# Modulo_shield_L6470-28.net
KiCad netlist of a schematic drawn in EAGLE
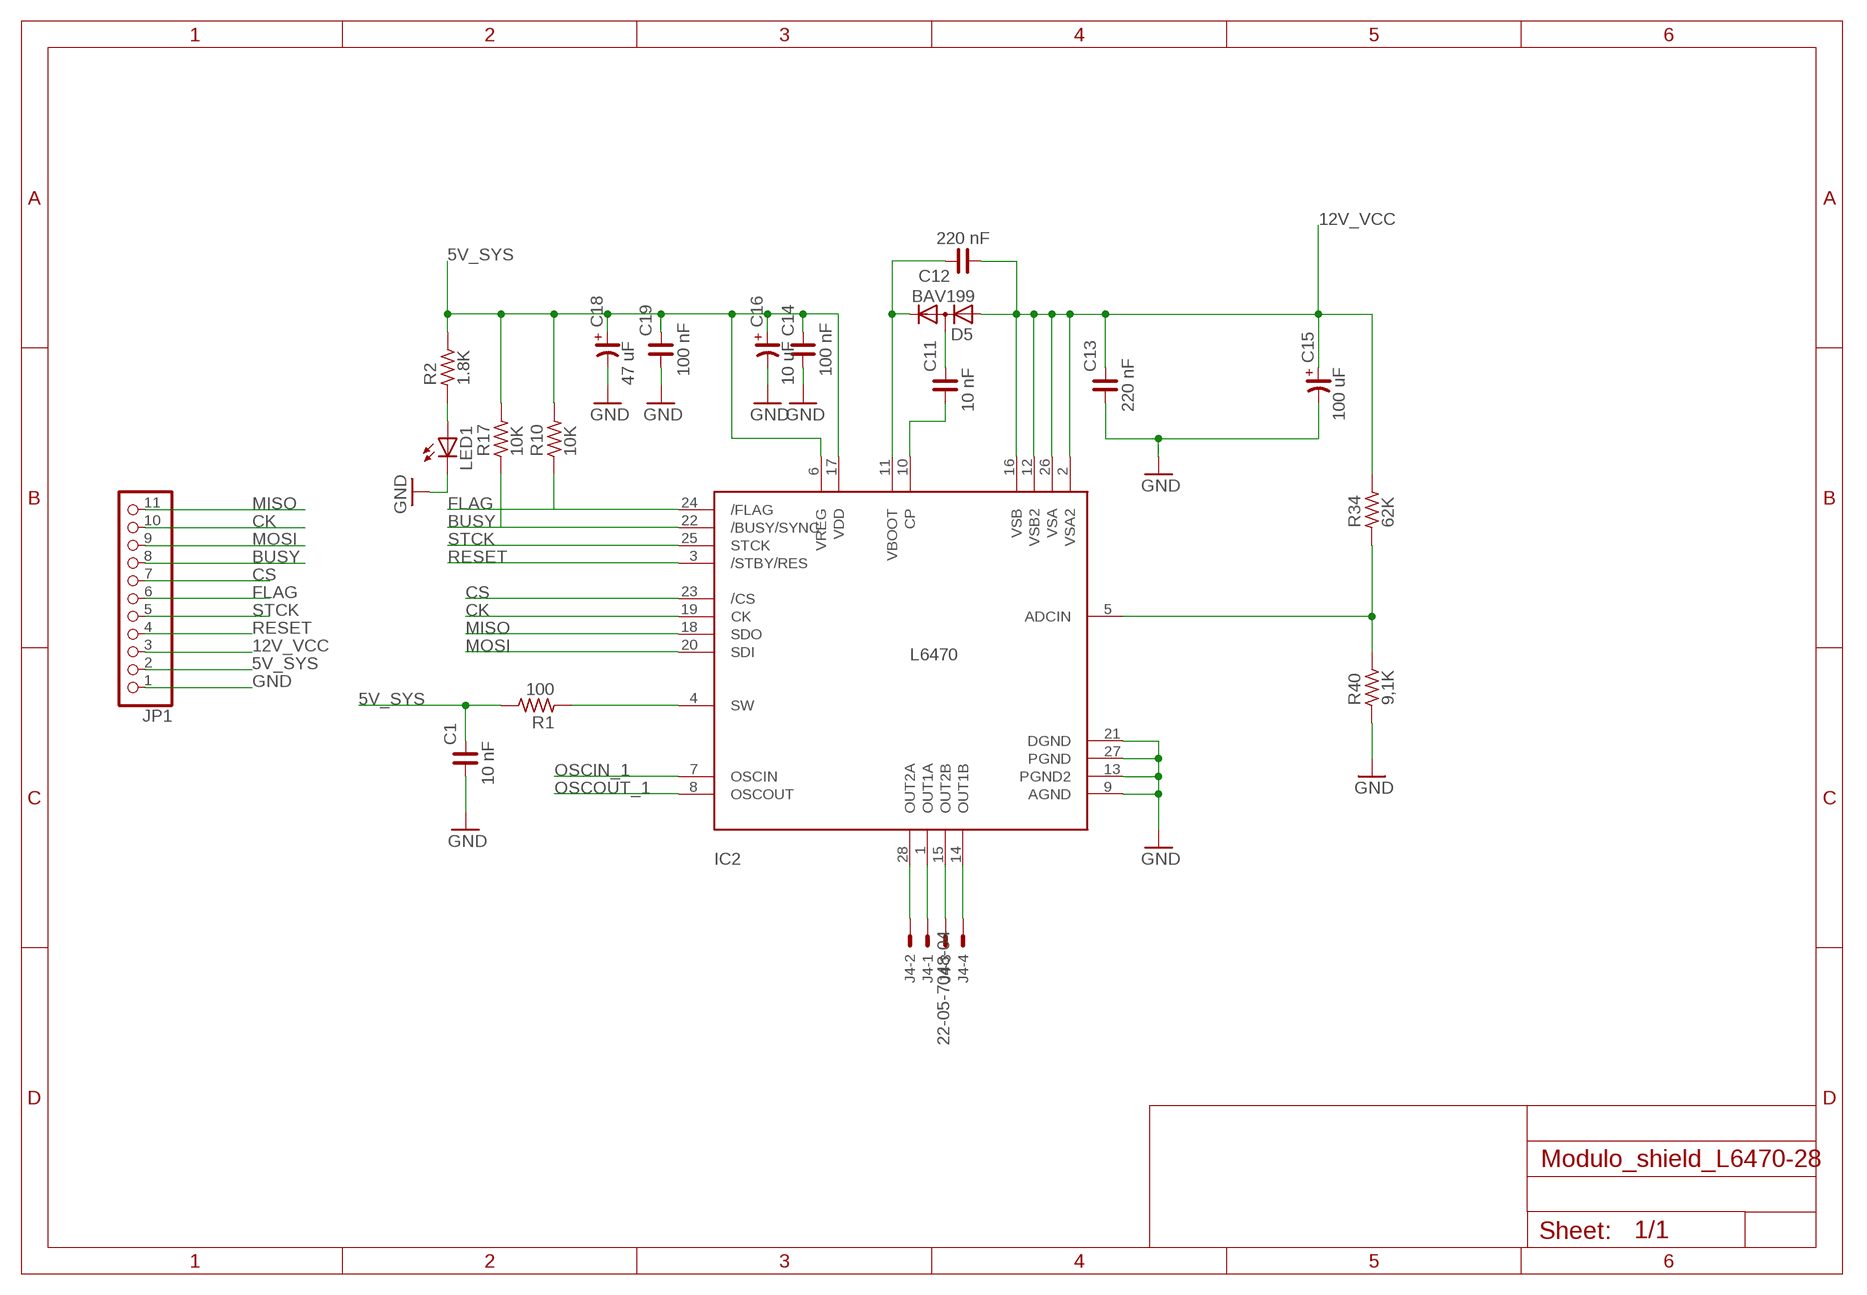
[diagram p0: schematic, sheet 1]

(export (version "E")
  (design (tool "Eeschema 10.0.6"))
  (components
    (comp (ref "C1")
      (value "10 nF")
      (footprint "eagle-import:C1206")
      (libsource (lib "eagle-import") (part "C_1206"))
    )
    (comp (ref "C11")
      (value "10 nF")
      (footprint "eagle-import:C1206")
      (libsource (lib "eagle-import") (part "C_1206"))
    )
    (comp (ref "C12")
      (value "220 nF")
      (footprint "eagle-import:C1206")
      (libsource (lib "eagle-import") (part "C_1206"))
    )
    (comp (ref "C13")
      (value "220 nF")
      (footprint "eagle-import:C1206")
      (libsource (lib "eagle-import") (part "C_1206"))
    )
    (comp (ref "C14")
      (value "100 nF")
      (footprint "eagle-import:C1206")
      (libsource (lib "eagle-import") (part "C_1206"))
    )
    (comp (ref "C15")
      (value "100 uF")
      (footprint "eagle-import:CSV-D")
      (libsource (lib "eagle-import") (part "CP_SV-D"))
    )
    (comp (ref "C16")
      (value "10 uF")
      (footprint "eagle-import:CSV-B")
      (libsource (lib "eagle-import") (part "CP_SV-B"))
    )
    (comp (ref "C18")
      (value "47 uF")
      (footprint "eagle-import:CSV-B")
      (libsource (lib "eagle-import") (part "CP_SV-B"))
    )
    (comp (ref "C19")
      (value "100 nF")
      (footprint "eagle-import:C1206")
      (libsource (lib "eagle-import") (part "C_1206"))
    )
    (comp (ref "D5")
      (value "BAV199")
      (footprint "eagle-import:SOT23")
      (libsource (lib "eagle-import") (part "BAV199"))
    )
    (comp (ref "IC2")
      (value "L6470")
      (footprint "eagle-import:HTSSOP28")
      (libsource (lib "eagle-import") (part "L6470"))
    )
    (comp (ref "J4")
      (value "22-05-7048-04")
      (footprint "eagle-import:7395-04")
      (libsource (lib "eagle-import") (part "22-?-0405-7048"))
    )
    (comp (ref "JP1")
      (value "PINHD-1X11/90")
      (footprint "eagle-import:1X11_90")
      (libsource (lib "eagle-import") (part "PINHD-1X11/90"))
    )
    (comp (ref "LED1")
      (value "LEDCHIPLED_1206")
      (footprint "eagle-import:CHIPLED_1206")
      (libsource (lib "eagle-import") (part "LEDCHIPLED_1206"))
    )
    (comp (ref "R1")
      (value "100")
      (footprint "eagle-import:R1206")
      (libsource (lib "eagle-import") (part "R_1206"))
    )
    (comp (ref "R2")
      (value "1.8K")
      (footprint "eagle-import:R1206")
      (libsource (lib "eagle-import") (part "R_1206"))
    )
    (comp (ref "R10")
      (value "10K")
      (footprint "eagle-import:R1206")
      (libsource (lib "eagle-import") (part "R_1206"))
    )
    (comp (ref "R17")
      (value "10K")
      (footprint "eagle-import:R1206")
      (libsource (lib "eagle-import") (part "R_1206"))
    )
    (comp (ref "R34")
      (value "62K")
      (footprint "eagle-import:R1206")
      (libsource (lib "eagle-import") (part "R_1206"))
    )
    (comp (ref "R40")
      (value "9,1K")
      (footprint "eagle-import:R1206")
      (libsource (lib "eagle-import") (part "R_1206"))
    )
  )
  (nets
    (net (code "1") (name "/5V_SYS") (class "Default")
      (node (ref "C1") (pin "2") (pinfunction "2_2") (pintype "passive"))
      (node (ref "C14") (pin "2") (pinfunction "2_2") (pintype "passive"))
      (node (ref "C16") (pin "+") (pinfunction "+_+") (pintype "passive"))
      (node (ref "C18") (pin "+") (pinfunction "+_+") (pintype "passive"))
      (node (ref "C19") (pin "2") (pinfunction "2_2") (pintype "passive"))
      (node (ref "IC2") (pin "17") (pinfunction "VDD_17") (pintype "power_in"))
      (node (ref "IC2") (pin "6") (pinfunction "VREG_6") (pintype "power_in"))
      (node (ref "JP1") (pin "2") (pinfunction "2_2") (pintype "passive"))
      (node (ref "R1") (pin "2") (pinfunction "2_2") (pintype "passive"))
      (node (ref "R10") (pin "2") (pinfunction "2_2") (pintype "passive"))
      (node (ref "R17") (pin "2") (pinfunction "2_2") (pintype "passive"))
      (node (ref "R2") (pin "2") (pinfunction "2_2") (pintype "passive"))
    )
    (net (code "2") (name "/12V_VCC") (class "Default")
      (node (ref "C12") (pin "1") (pinfunction "1_1") (pintype "passive"))
      (node (ref "C13") (pin "2") (pinfunction "2_2") (pintype "passive"))
      (node (ref "C15") (pin "+") (pinfunction "+_+") (pintype "passive"))
      (node (ref "D5") (pin "1") (pinfunction "A_1") (pintype "passive"))
      (node (ref "IC2") (pin "12") (pinfunction "VSB2_12") (pintype "power_in"))
      (node (ref "IC2") (pin "16") (pinfunction "VSB_16") (pintype "power_in"))
      (node (ref "IC2") (pin "2") (pinfunction "VSA2_2") (pintype "power_in"))
      (node (ref "IC2") (pin "26") (pinfunction "VSA_26") (pintype "power_in"))
      (node (ref "JP1") (pin "3") (pinfunction "3_3") (pintype "passive"))
      (node (ref "R34") (pin "2") (pinfunction "2_2") (pintype "passive"))
    )
    (net (code "3") (name "/BUSY") (class "Default")
      (node (ref "IC2") (pin "22") (pinfunction "/BUSY/SYNC_22") (pintype "output"))
      (node (ref "JP1") (pin "8") (pinfunction "8_8") (pintype "passive"))
      (node (ref "R17") (pin "1") (pinfunction "1_1") (pintype "passive"))
    )
    (net (code "4") (name "/CK") (class "Default")
      (node (ref "IC2") (pin "19") (pinfunction "CK_19") (pintype "input"))
      (node (ref "JP1") (pin "10") (pinfunction "10_10") (pintype "passive"))
    )
    (net (code "5") (name "/CS") (class "Default")
      (node (ref "IC2") (pin "23") (pinfunction "/CS_23") (pintype "input"))
      (node (ref "JP1") (pin "7") (pinfunction "7_7") (pintype "passive"))
    )
    (net (code "6") (name "/FLAG") (class "Default")
      (node (ref "IC2") (pin "24") (pinfunction "/FLAG_24") (pintype "output"))
      (node (ref "JP1") (pin "6") (pinfunction "6_6") (pintype "passive"))
      (node (ref "R10") (pin "1") (pinfunction "1_1") (pintype "passive"))
    )
    (net (code "7") (name "/MISO") (class "Default")
      (node (ref "IC2") (pin "18") (pinfunction "SDO_18") (pintype "output"))
      (node (ref "JP1") (pin "11") (pinfunction "11_11") (pintype "passive"))
    )
    (net (code "8") (name "/MOSI") (class "Default")
      (node (ref "IC2") (pin "20") (pinfunction "SDI_20") (pintype "input"))
      (node (ref "JP1") (pin "9") (pinfunction "9_9") (pintype "passive"))
    )
    (net (code "9") (name "/OSCIN_1") (class "Default")
      (node (ref "IC2") (pin "7") (pinfunction "OSCIN_7") (pintype "input"))
    )
    (net (code "10") (name "/OSCOUT_1") (class "Default")
      (node (ref "IC2") (pin "8") (pinfunction "OSCOUT_8") (pintype "output"))
    )
    (net (code "11") (name "/RESET") (class "Default")
      (node (ref "IC2") (pin "3") (pinfunction "/STBY/RES_3") (pintype "input"))
      (node (ref "JP1") (pin "4") (pinfunction "4_4") (pintype "passive"))
    )
    (net (code "12") (name "/STCK") (class "Default")
      (node (ref "IC2") (pin "25") (pinfunction "STCK_25") (pintype "input"))
      (node (ref "JP1") (pin "5") (pinfunction "5_5") (pintype "passive"))
    )
    (net (code "13") (name "GND") (class "Default")
      (node (ref "C1") (pin "1") (pinfunction "1_1") (pintype "passive"))
      (node (ref "C13") (pin "1") (pinfunction "1_1") (pintype "passive"))
      (node (ref "C14") (pin "1") (pinfunction "1_1") (pintype "passive"))
      (node (ref "C15") (pin "-") (pinfunction "-_-") (pintype "passive"))
      (node (ref "C16") (pin "-") (pinfunction "-_-") (pintype "passive"))
      (node (ref "C18") (pin "-") (pinfunction "-_-") (pintype "passive"))
      (node (ref "C19") (pin "1") (pinfunction "1_1") (pintype "passive"))
      (node (ref "IC2") (pin "13") (pinfunction "PGND2_13") (pintype "power_in"))
      (node (ref "IC2") (pin "21") (pinfunction "DGND_21") (pintype "power_in"))
      (node (ref "IC2") (pin "27") (pinfunction "PGND_27") (pintype "power_in"))
      (node (ref "IC2") (pin "9") (pinfunction "AGND_9") (pintype "power_in"))
      (node (ref "JP1") (pin "1") (pinfunction "1_1") (pintype "passive"))
      (node (ref "LED1") (pin "C") (pinfunction "C_C") (pintype "passive"))
      (node (ref "R40") (pin "1") (pinfunction "1_1") (pintype "passive"))
    )
    (net (code "14") (name "Net-(D5-AC)") (class "Default")
      (node (ref "C11") (pin "2") (pinfunction "2_2") (pintype "passive"))
      (node (ref "D5") (pin "3") (pinfunction "AC_3") (pintype "passive"))
    )
    (net (code "15") (name "Net-(D5-C)") (class "Default")
      (node (ref "C12") (pin "2") (pinfunction "2_2") (pintype "passive"))
      (node (ref "D5") (pin "2") (pinfunction "C_2") (pintype "passive"))
      (node (ref "IC2") (pin "11") (pinfunction "VBOOT_11") (pintype "power_in"))
    )
    (net (code "16") (name "Net-(IC2-ADCIN)") (class "Default")
      (node (ref "IC2") (pin "5") (pinfunction "ADCIN_5") (pintype "input"))
      (node (ref "R34") (pin "1") (pinfunction "1_1") (pintype "passive"))
      (node (ref "R40") (pin "2") (pinfunction "2_2") (pintype "passive"))
    )
    (net (code "17") (name "Net-(IC2-CP)") (class "Default")
      (node (ref "C11") (pin "1") (pinfunction "1_1") (pintype "passive"))
      (node (ref "IC2") (pin "10") (pinfunction "CP_10") (pintype "output"))
    )
    (net (code "18") (name "Net-(IC2-OUT1A)") (class "Default")
      (node (ref "IC2") (pin "1") (pinfunction "OUT1A_1") (pintype "output"))
      (node (ref "J4") (pin "1") (pinfunction "S_1") (pintype "passive"))
    )
    (net (code "19") (name "Net-(IC2-OUT1B)") (class "Default")
      (node (ref "IC2") (pin "14") (pinfunction "OUT1B_14") (pintype "output"))
      (node (ref "J4") (pin "4") (pinfunction "S_4") (pintype "passive"))
    )
    (net (code "20") (name "Net-(IC2-OUT2A)") (class "Default")
      (node (ref "IC2") (pin "28") (pinfunction "OUT2A_28") (pintype "output"))
      (node (ref "J4") (pin "2") (pinfunction "S_2") (pintype "passive"))
    )
    (net (code "21") (name "Net-(IC2-OUT2B)") (class "Default")
      (node (ref "IC2") (pin "15") (pinfunction "OUT2B_15") (pintype "output"))
      (node (ref "J4") (pin "3") (pinfunction "S_3") (pintype "passive"))
    )
    (net (code "22") (name "Net-(IC2-SW)") (class "Default")
      (node (ref "IC2") (pin "4") (pinfunction "SW_4") (pintype "input"))
      (node (ref "R1") (pin "1") (pinfunction "1_1") (pintype "passive"))
    )
    (net (code "23") (name "Net-(LED1-PadA)") (class "Default")
      (node (ref "LED1") (pin "A") (pinfunction "A_A") (pintype "passive"))
      (node (ref "R2") (pin "1") (pinfunction "1_1") (pintype "passive"))
    )
  )
)
